# 4T_-.net
KiCad netlist of a schematic drawn in EasyEDA Pro
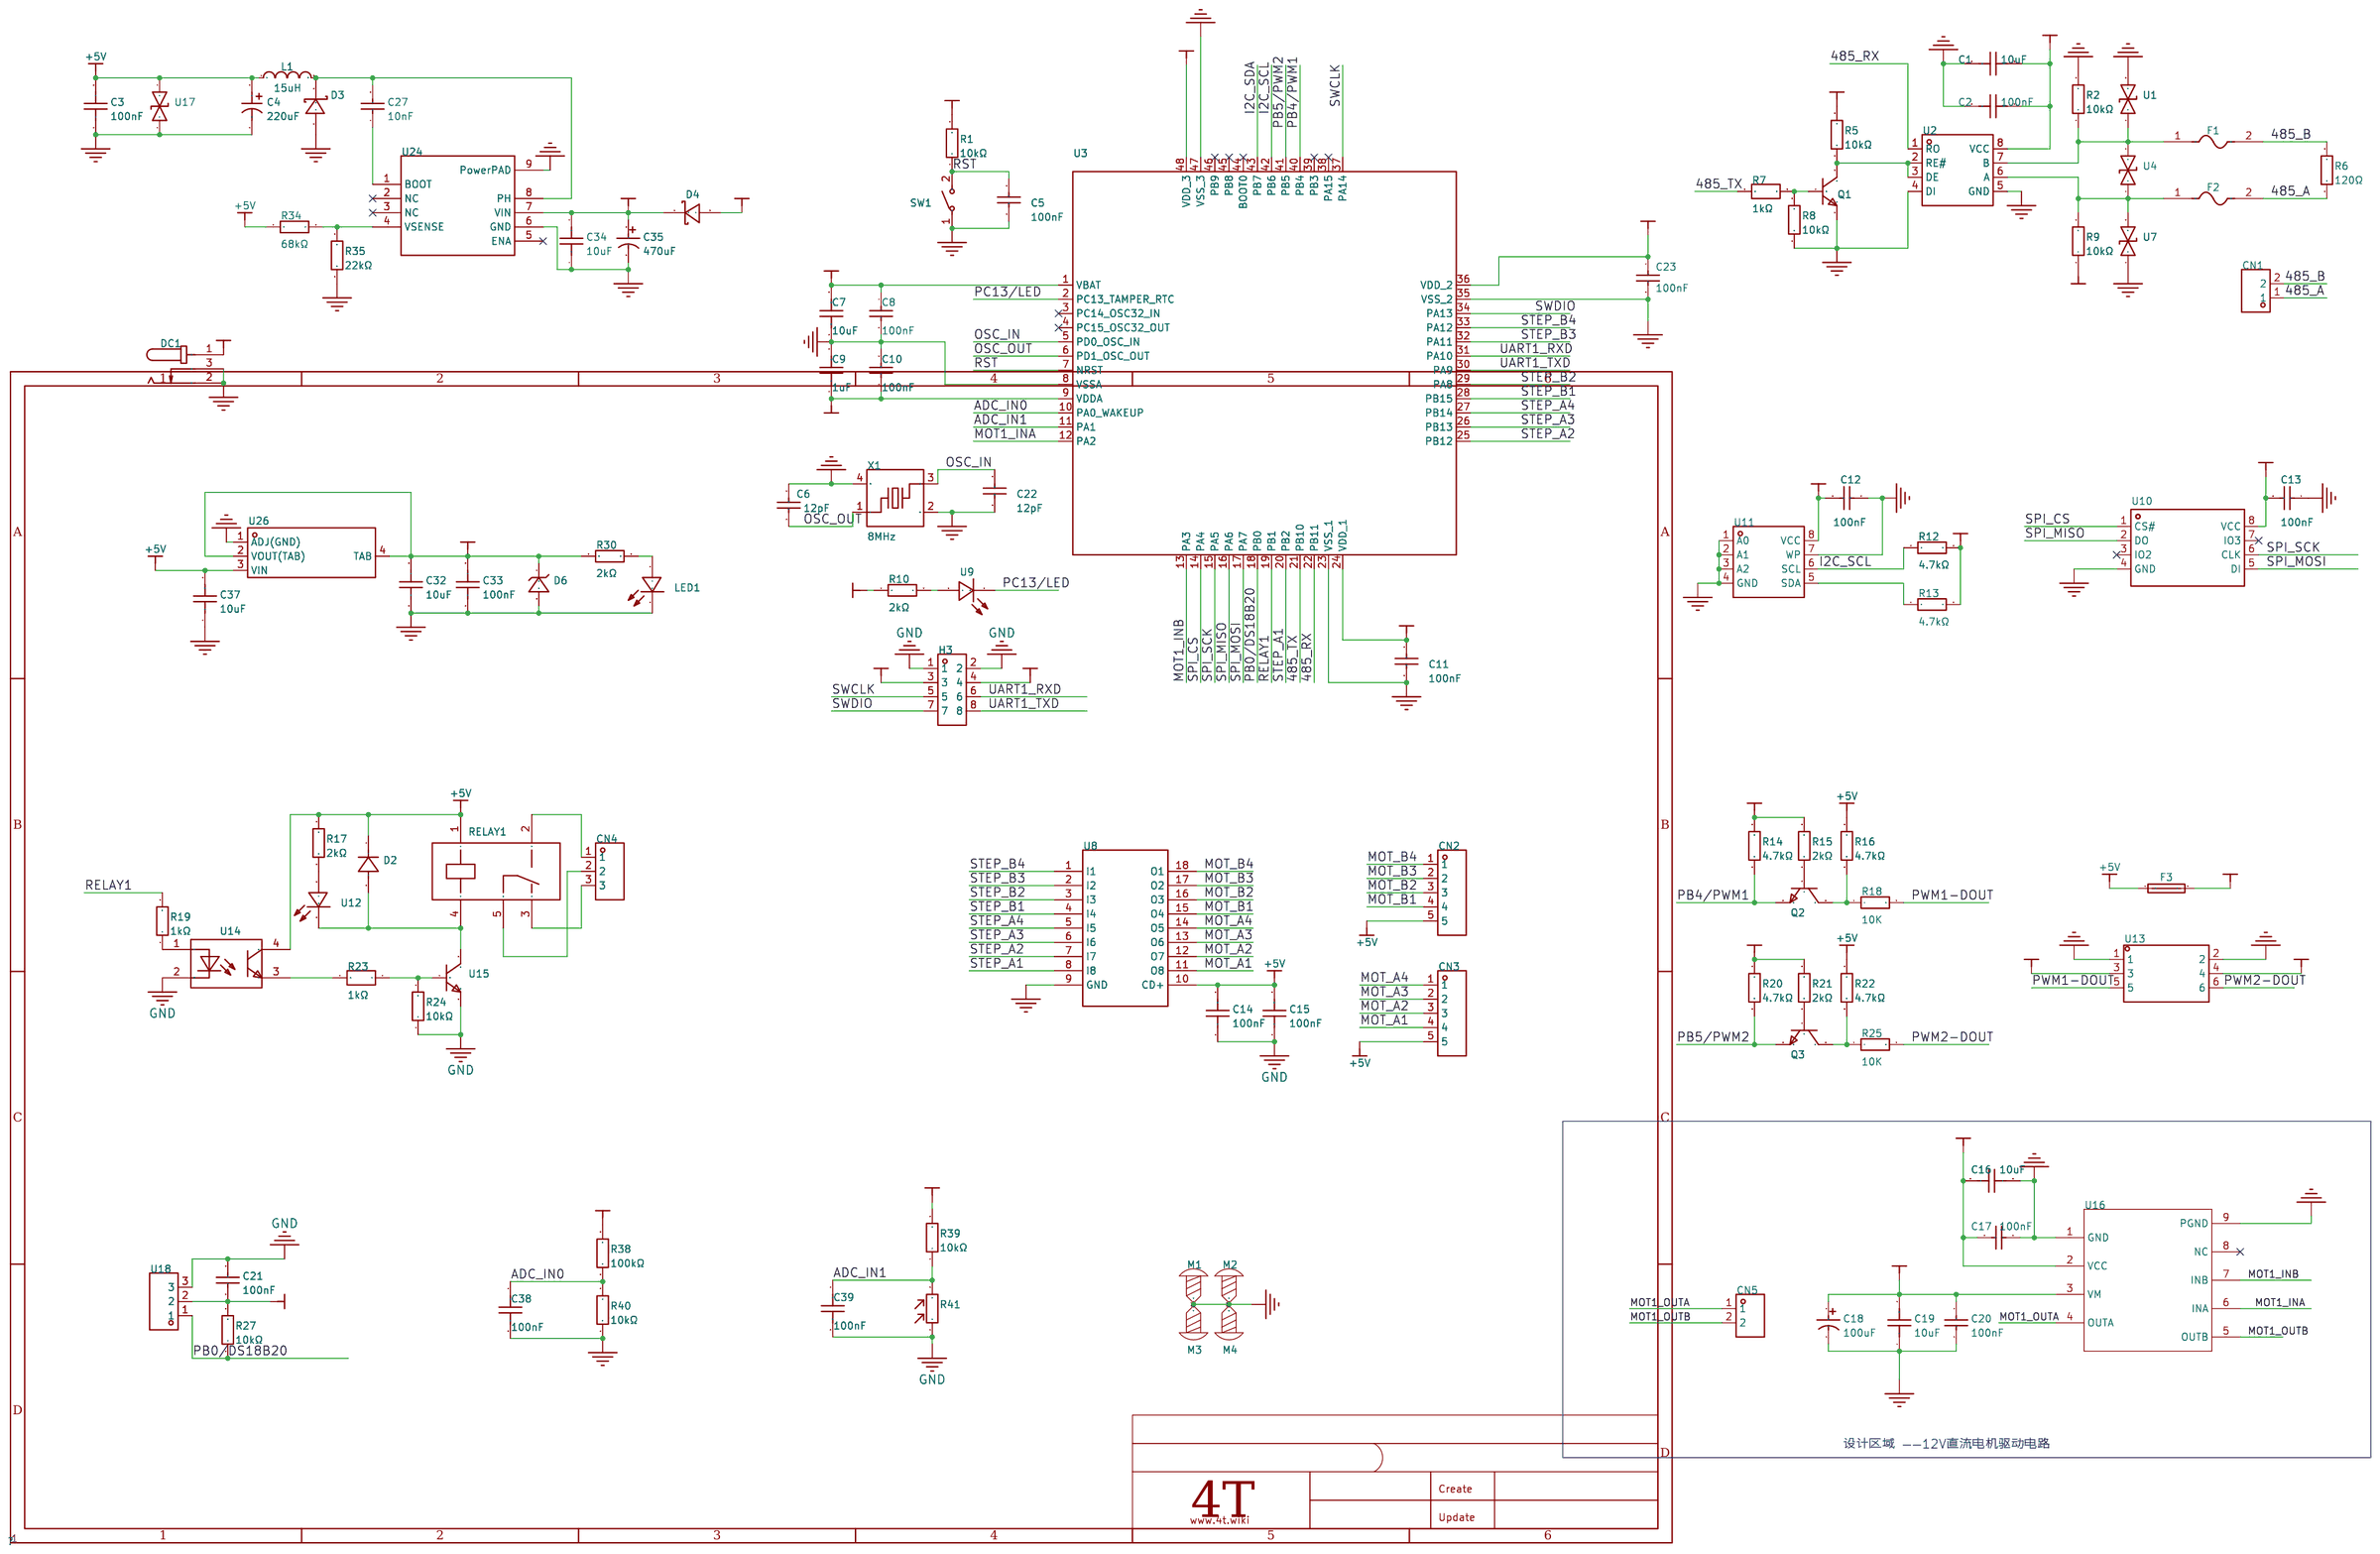
[diagram p0: schematic sheet]

(export (version "E")
  (design (tool "Eeschema 10.0.6"))
  (components
    (comp (ref "C1")
      (value "10uF")
      (footprint "easyedapro:C0603")
      (fields
        (field (name "Manufacturer Part") "CC0603KRX5R6BB106")
        (field (name "Manufacturer") "YAGEO(国巨)")
      )
      (libsource (lib "easyedapro") (part "CC0603KRX5R6BB106"))
    )
    (comp (ref "C2") (value "100nF") (libsource (lib "easyedapro") (part "CC0603KRX7R9BB104")))
    (comp (ref "C3")
      (value "100nF")
      (footprint "easyedapro:C0805")
      (fields
        (field (name "Manufacturer Part") "CC0805KRX7R9BB104")
        (field (name "Manufacturer") "YAGEO(国巨)")
      )
      (libsource (lib "easyedapro") (part "CC0805KRX7R9BB104"))
    )
    (comp (ref "C4")
      (value "220uF")
      (footprint "easyedapro:CAP-SMD_BD6.3-L6.6-W6.6-FD")
      (fields (field (name "Manufacturer Part") "189RV0019") (field (name "Manufacturer") "KNSCHA(科尼盛)"))
      (libsource (lib "easyedapro") (part "189RV0019"))
    )
    (comp (ref "C5") (value "100nF") (libsource (lib "easyedapro") (part "CC0603KRX7R8BB104")))
    (comp (ref "C6")
      (value "12pF")
      (footprint "easyedapro:C0603")
      (fields
        (field (name "Manufacturer Part") "CL10C120JB8NNNC")
        (field (name "Manufacturer") "SAMSUNG(三星)")
      )
      (libsource (lib "easyedapro") (part "CL10C120JB8NNNC"))
    )
    (comp (ref "C7")
      (value "10uF")
      (footprint "easyedapro:C0603")
      (fields
        (field (name "Manufacturer Part") "CL10A106KP8NNNC")
        (field (name "Manufacturer") "SAMSUNG(三星)")
      )
      (libsource (lib "easyedapro") (part "CL10A106KP8NNNC"))
    )
    (comp (ref "C8") (value "100nF") (libsource (lib "easyedapro") (part "CC0603KRX7R8BB104")))
    (comp (ref "C9")
      (value "1uF")
      (footprint "easyedapro:C0603")
      (fields
        (field (name "Manufacturer Part") "CC0603KRX7R9BB105")
        (field (name "Manufacturer") "YAGEO(国巨)")
      )
      (libsource (lib "easyedapro") (part "CC0603KRX7R9BB105"))
    )
    (comp (ref "C10") (value "100nF") (libsource (lib "easyedapro") (part "CC0603KRX7R8BB104")))
    (comp (ref "C11") (value "100nF") (libsource (lib "easyedapro") (part "CC0603KRX7R8BB104")))
    (comp (ref "C12") (value "100nF") (libsource (lib "easyedapro") (part "CC0603KRX7R8BB104")))
    (comp (ref "C13") (value "100nF") (libsource (lib "easyedapro") (part "CC0603KRX7R8BB104")))
    (comp (ref "C14")
      (value "100nF")
      (footprint "easyedapro:C0805")
      (fields
        (field (name "Manufacturer Part") "CL21A226MAQNNNE")
        (field (name "Manufacturer") "SAMSUNG(三星)")
      )
      (libsource (lib "easyedapro") (part "CL21A226MAQNNNE"))
    )
    (comp (ref "C15")
      (value "100nF")
      (footprint "easyedapro:C0805")
      (fields
        (field (name "Manufacturer Part") "CL21A226MAQNNNE")
        (field (name "Manufacturer") "SAMSUNG(三星)")
      )
      (libsource (lib "easyedapro") (part "CL21A226MAQNNNE"))
    )
    (comp (ref "C16")
      (value "10uF")
      (footprint "easyedapro:C0603")
      (fields
        (field (name "Manufacturer Part") "CL10A106MA8NRNC")
        (field (name "Manufacturer") "SAMSUNG(三星)")
      )
      (libsource (lib "easyedapro") (part "CL10A106MA8NRNC"))
    )
    (comp (ref "C17")
      (value "100nF")
      (footprint "easyedapro:C0603")
      (fields
        (field (name "Manufacturer Part") "CC0603KRX7R8BB104")
        (field (name "Manufacturer") "YAGEO(国巨)")
      )
      (libsource (lib "easyedapro") (part "CC0603KRX7R8BB104"))
    )
    (comp (ref "C18")
      (value "100uF")
      (footprint "easyedapro:CAP-SMD_BD6.3-L6.6-W6.6-LS7.2-R-RD")
      (fields (field (name "Manufacturer Part") "RVE1V101M0607") (field (name "Manufacturer") "ROQANG(容强)"))
      (libsource (lib "easyedapro") (part "RVE1V101M0607-C99837"))
    )
    (comp (ref "C19")
      (value "10uF")
      (footprint "easyedapro:C0603")
      (fields
        (field (name "Manufacturer Part") "CL10A106MA8NRNC")
        (field (name "Manufacturer") "SAMSUNG(三星)")
      )
      (libsource (lib "easyedapro") (part "CL10A106MA8NRNC"))
    )
    (comp (ref "C20")
      (value "100nF")
      (footprint "easyedapro:C0603")
      (fields
        (field (name "Manufacturer Part") "CC0603KRX7R8BB104")
        (field (name "Manufacturer") "YAGEO(国巨)")
      )
      (libsource (lib "easyedapro") (part "CC0603KRX7R8BB104"))
    )
    (comp (ref "C21") (value "100nF") (libsource (lib "easyedapro") (part "CC0603KRX7R8BB104")))
    (comp (ref "C22")
      (value "12pF")
      (footprint "easyedapro:C0603")
      (fields
        (field (name "Manufacturer Part") "CL10C120JB8NNNC")
        (field (name "Manufacturer") "SAMSUNG(三星)")
      )
      (libsource (lib "easyedapro") (part "CL10C120JB8NNNC"))
    )
    (comp (ref "C23") (value "100nF") (libsource (lib "easyedapro") (part "CC0603KRX7R8BB104")))
    (comp (ref "C27")
      (value "10nF")
      (footprint "easyedapro:C0603")
      (fields (field (name "Manufacturer Part") "0603B103K500NT") (field (name "Manufacturer") "FH(风华)"))
      (libsource (lib "easyedapro") (part "0603B103K500NT"))
    )
    (comp (ref "C32")
      (value "10uF")
      (footprint "easyedapro:C0603")
      (fields
        (field (name "Manufacturer Part") "CC0603MRX5R8BB106")
        (field (name "Manufacturer") "YAGEO(国巨)")
      )
      (libsource (lib "easyedapro") (part "CC0603MRX5R8BB106"))
    )
    (comp (ref "C33") (value "100nF") (libsource (lib "") (part "CC0603KRX7R9BB104_1")))
    (comp (ref "C34")
      (value "10uF")
      (footprint "easyedapro:C0805")
      (fields
        (field (name "Manufacturer Part") "GRM21BR61H106KE43L")
        (field (name "Manufacturer") "muRata(村田)")
      )
      (libsource (lib "easyedapro") (part "GRM21BR61H106KE43L"))
    )
    (comp (ref "C35")
      (value "470uF")
      (footprint "easyedapro:CAP-SMD_BD10.0-L10.3-W10.3-LS11.0-R-RD")
      (fields (field (name "Manufacturer Part") "RVT1V471M1010") (field (name "Manufacturer") "ROQANG(容强)"))
      (libsource (lib "easyedapro") (part "RVT1V471M1010-C72519"))
    )
    (comp (ref "C37")
      (value "10uF")
      (footprint "easyedapro:C0603")
      (fields
        (field (name "Manufacturer Part") "CC0603MRX5R8BB106")
        (field (name "Manufacturer") "YAGEO(国巨)")
      )
      (libsource (lib "easyedapro") (part "CC0603MRX5R8BB106"))
    )
    (comp (ref "C38")
      (value "100nF")
      (footprint "easyedapro:C0603")
      (fields
        (field (name "Manufacturer Part") "CC0603KRX7R9BB104")
        (field (name "Manufacturer") "YAGEO(国巨)")
      )
      (libsource (lib "easyedapro") (part "CC0603KRX7R9BB104"))
    )
    (comp (ref "C39")
      (value "100nF")
      (footprint "easyedapro:C0603")
      (fields
        (field (name "Manufacturer Part") "CC0603KRX7R9BB104")
        (field (name "Manufacturer") "YAGEO(国巨)")
      )
      (libsource (lib "easyedapro") (part "CC0603KRX7R9BB104"))
    )
    (comp (ref "CN1")
      (value "~")
      (footprint "easyedapro:CONN-TH_P5.00_KF2EDGR-5.0-2P")
      (fields (field (name "Manufacturer Part") "KF2EDGR-5.0-2P") (field (name "Manufacturer") "KEFA(科发)"))
      (libsource (lib "easyedapro") (part "KF2EDGR-5.0-2P"))
    )
    (comp (ref "CN2")
      (value "~")
      (footprint "easyedapro:CONN-TH_5P-P2.54_XH-5AW_C2908614")
      (fields (field (name "Manufacturer Part") "XH-5AW") (field (name "Manufacturer") "HCTL(华灿天禄)"))
      (libsource (lib "easyedapro") (part "XH-5AW_C2908614"))
    )
    (comp (ref "CN3")
      (value "~")
      (footprint "easyedapro:CONN-TH_5P-P2.54_XH-5AW_C2908614")
      (fields (field (name "Manufacturer Part") "XH-5AW") (field (name "Manufacturer") "HCTL(华灿天禄)"))
      (libsource (lib "easyedapro") (part "XH-5AW_C2908614"))
    )
    (comp (ref "CN4")
      (value "~")
      (footprint "easyedapro:CONN-TH_3P-P5.00_KF2EDGR-5.0-3P")
      (fields (field (name "Manufacturer Part") "KF2EDGR-5.0-3P") (field (name "Manufacturer") "KEFA(科发)"))
      (libsource (lib "easyedapro") (part "KF2EDGR-5.0-3P"))
    )
    (comp (ref "CN5")
      (value "~")
      (footprint "easyedapro:CONN-TH_2P-P2.50_ZX-XH2.54-2PWZ")
      (fields
        (field (name "Manufacturer Part") "ZX-XH2.54-2PWZ")
        (field (name "Manufacturer") "Megastar(兆星)")
      )
      (libsource (lib "easyedapro") (part "ZX-XH2.54-2PWZ"))
    )
    (comp (ref "D2") (value "1N4007") (libsource (lib "easyedapro") (part "1N4007_C727081")))
    (comp (ref "D3")
      (value "SS34")
      (footprint "easyedapro:SMA_L4.3-W2.6-LS5.2-RD")
      (fields (field (name "Manufacturer") "MDD(辰达半导体)"))
      (libsource (lib "easyedapro") (part "SS34_C8678"))
    )
    (comp (ref "D4")
      (value "SS34")
      (footprint "easyedapro:SMA_L4.3-W2.6-LS5.2-RD")
      (fields (field (name "Manufacturer") "MDD(辰达半导体)"))
      (libsource (lib "easyedapro") (part "SS34_C8678"))
    )
    (comp (ref "D6")
      (value "~")
      (footprint "easyedapro:SMB_L4.3-W3.6-LS5.3-RD")
      (fields (field (name "Manufacturer Part") "SMBJ3.3A") (field (name "Manufacturer") "RUILON(瑞隆源)"))
      (libsource (lib "easyedapro") (part "SMBJ3.3A_C2990571"))
    )
    (comp (ref "DC1")
      (value "~")
      (footprint "easyedapro:CONN-TH_DC-005-2.5A-2.0")
      (fields
        (field (name "Manufacturer Part") "DC-005-2.5A-2.0")
        (field (name "Manufacturer") "XKB Connectivity(中国星坤)")
      )
      (libsource (lib "easyedapro") (part "DC-005-2.5A-2.0"))
    )
    (comp (ref "F1")
      (value "~")
      (footprint "easyedapro:F0805")
      (fields (field (name "Manufacturer Part") "0805L100/12AR") (field (name "Manufacturer") "LUTE(陆特)"))
      (libsource (lib "easyedapro") (part "0805l100/12ar"))
    )
    (comp (ref "F2")
      (value "~")
      (footprint "easyedapro:F0805")
      (fields (field (name "Manufacturer Part") "0805L100/12AR") (field (name "Manufacturer") "LUTE(陆特)"))
      (libsource (lib "easyedapro") (part "0805l100/12ar"))
    )
    (comp (ref "F3")
      (value "~")
      (footprint "easyedapro:F0603")
      (fields (field (name "Manufacturer Part") "BSMD0603L-100") (field (name "Manufacturer") "BHFUSE(佰宏)"))
      (libsource (lib "easyedapro") (part "BSMD0603L-100"))
    )
    (comp (ref "H3")
      (value "~")
      (footprint "easyedapro:HDR-TH_8P-P2.54-V-M-R2-C4-S2.54")
      (fields (field (name "Manufacturer Part") "PZ254V-12-8P") (field (name "Manufacturer") "XFCN(兴飞)"))
      (libsource (lib "easyedapro") (part "PZ254V-12-8P"))
    )
    (comp (ref "L1")
      (value "15uH")
      (footprint "easyedapro:IND-SMD_L7.1-W6.6_SLO0618H")
      (fields
        (field (name "Manufacturer Part") "SLO0630H150MTT")
        (field (name "Manufacturer") "Sunltech(韩国顺磁)")
      )
      (libsource (lib "easyedapro") (part "SLO0630H150MTT"))
    )
    (comp (ref "LED1")
      (value "~")
      (footprint "easyedapro:LED0603-RD")
      (fields (field (name "Manufacturer Part") "KT-0603R") (field (name "Manufacturer") "KENTO"))
      (libsource (lib "easyedapro") (part "KT-0603R"))
    )
    (comp (ref "M1")
      (value "~")
      (footprint "easyedapro:LQ_M3螺丝")
      (description "Round,210")
      (libsource (lib "easyedapro") (part "M3螺丝孔"))
    )
    (comp (ref "M2")
      (value "~")
      (footprint "easyedapro:LQ_M3螺丝")
      (description "Round,210")
      (libsource (lib "easyedapro") (part "M3螺丝孔"))
    )
    (comp (ref "M3")
      (value "~")
      (footprint "easyedapro:LQ_M3螺丝")
      (description "Round,210")
      (libsource (lib "easyedapro") (part "M3螺丝孔"))
    )
    (comp (ref "M4")
      (value "~")
      (footprint "easyedapro:LQ_M3螺丝")
      (description "Round,210")
      (libsource (lib "easyedapro") (part "M3螺丝孔"))
    )
    (comp (ref "Q1")
      (value "~")
      (footprint "easyedapro:SOT-23-3_L2.9-W1.3-P1.90-LS2.4-BR")
      (fields (field (name "Manufacturer Part") "MMBT3904") (field (name "Manufacturer") "宏迦橙"))
      (libsource (lib "easyedapro") (part "MMBT3904_C7420353"))
    )
    (comp (ref "Q2")
      (value "S8050-J3Y")
      (footprint "easyedapro:SOT-23-3_L2.9-W1.6-P1.90-LS2.8-BR")
      (fields (field (name "Manufacturer Part") "S8050") (field (name "Manufacturer") "CJ(江苏长电/长晶)"))
      (libsource (lib "easyedapro") (part "S8050_C105433"))
    )
    (comp (ref "Q3")
      (value "S8050-J3Y")
      (footprint "easyedapro:SOT-23-3_L2.9-W1.6-P1.90-LS2.8-BR")
      (fields (field (name "Manufacturer Part") "S8050") (field (name "Manufacturer") "CJ(江苏长电/长晶)"))
      (libsource (lib "easyedapro") (part "S8050_C105433"))
    )
    (comp (ref "R1")
      (value "10kΩ")
      (footprint "easyedapro:R0603")
      (fields
        (field (name "Manufacturer Part") "0603WAF1002T5E")
        (field (name "Manufacturer") "UNI-ROYAL(厚声)")
      )
      (libsource (lib "easyedapro") (part "0603WAF1002T5E"))
    )
    (comp (ref "R2") (value "10kΩ") (libsource (lib "easyedapro") (part "RC0603JR-0710KL")))
    (comp (ref "R5")
      (value "10kΩ")
      (footprint "easyedapro:R0603")
      (fields (field (name "Manufacturer Part") "RC0603JR-0710KL") (field (name "Manufacturer") "YAGEO(国巨)"))
      (libsource (lib "easyedapro") (part "RC0603JR-0710KL"))
    )
    (comp (ref "R6")
      (value "120Ω")
      (footprint "easyedapro:R0805")
      (fields
        (field (name "Manufacturer Part") "0805W8F1200T5E")
        (field (name "Manufacturer") "UNI-ROYAL(厚声)")
      )
      (libsource (lib "easyedapro") (part "0805W8F1200T5E"))
    )
    (comp (ref "R7")
      (value "1kΩ")
      (footprint "easyedapro:R0603")
      (fields (field (name "Manufacturer Part") "RT0603BRE071KL") (field (name "Manufacturer") "YAGEO(国巨)"))
      (libsource (lib "easyedapro") (part "RT0603BRE071KL"))
    )
    (comp (ref "R8")
      (value "10kΩ")
      (footprint "easyedapro:R0603")
      (fields (field (name "Manufacturer Part") "RC0603JR-0710KL") (field (name "Manufacturer") "YAGEO(国巨)"))
      (libsource (lib "easyedapro") (part "RC0603JR-0710KL"))
    )
    (comp (ref "R9") (value "10kΩ") (libsource (lib "easyedapro") (part "RC0603JR-0710KL")))
    (comp (ref "R10")
      (value "2kΩ")
      (footprint "easyedapro:R0603")
      (fields
        (field (name "Manufacturer Part") "0603WAF2001T5E")
        (field (name "Manufacturer") "UNI-ROYAL(厚声)")
      )
      (libsource (lib "easyedapro") (part "0603WAF2001T5E"))
    )
    (comp (ref "R12")
      (value "4.7kΩ")
      (footprint "easyedapro:R0603")
      (fields (field (name "Manufacturer Part") "RC0603FR-074K7L") (field (name "Manufacturer") "YAGEO(国巨)"))
      (libsource (lib "easyedapro") (part "RC0603FR-074K7L"))
    )
    (comp (ref "R13")
      (value "4.7kΩ")
      (footprint "easyedapro:R0603")
      (fields (field (name "Manufacturer Part") "RC0603FR-074K7L") (field (name "Manufacturer") "YAGEO(国巨)"))
      (libsource (lib "easyedapro") (part "RC0603FR-074K7L"))
    )
    (comp (ref "R14")
      (value "4.7kΩ")
      (footprint "easyedapro:R0603")
      (fields (field (name "Manufacturer Part") "RC0603FR-074K7L") (field (name "Manufacturer") "YAGEO(国巨)"))
      (libsource (lib "easyedapro") (part "RC0603FR-074K7L"))
    )
    (comp (ref "R15")
      (value "2kΩ")
      (footprint "easyedapro:R0603")
      (fields (field (name "Manufacturer Part") "RC0603FR-072KL") (field (name "Manufacturer") "YAGEO(国巨)"))
      (libsource (lib "easyedapro") (part "RC0603FR-072KL"))
    )
    (comp (ref "R16")
      (value "4.7kΩ")
      (footprint "easyedapro:R0603")
      (fields (field (name "Manufacturer Part") "RC0603FR-074K7L") (field (name "Manufacturer") "YAGEO(国巨)"))
      (libsource (lib "easyedapro") (part "RC0603FR-074K7L"))
    )
    (comp (ref "R17")
      (value "2kΩ")
      (footprint "easyedapro:R0603")
      (fields
        (field (name "Manufacturer Part") "0603WAF2001T5E")
        (field (name "Manufacturer") "UNI-ROYAL(厚声)")
      )
      (libsource (lib "easyedapro") (part "0603WAF2001T5E"))
    )
    (comp (ref "R18")
      (value "10K")
      (footprint "easyedapro:R0603")
      (fields (field (name "Manufacturer Part") "RC0603FR-071KL") (field (name "Manufacturer") "YAGEO(国巨)"))
      (libsource (lib "easyedapro") (part "RC0603FR-071KL"))
    )
    (comp (ref "R19") (value "1kΩ") (libsource (lib "easyedapro") (part "RC0603FR-071KL")))
    (comp (ref "R20")
      (value "4.7kΩ")
      (footprint "easyedapro:R0603")
      (fields (field (name "Manufacturer Part") "RC0603FR-074K7L") (field (name "Manufacturer") "YAGEO(国巨)"))
      (libsource (lib "easyedapro") (part "RC0603FR-074K7L"))
    )
    (comp (ref "R21")
      (value "2kΩ")
      (footprint "easyedapro:R0603")
      (fields (field (name "Manufacturer Part") "RC0603FR-072KL") (field (name "Manufacturer") "YAGEO(国巨)"))
      (libsource (lib "easyedapro") (part "RC0603FR-072KL"))
    )
    (comp (ref "R22")
      (value "4.7kΩ")
      (footprint "easyedapro:R0603")
      (fields (field (name "Manufacturer Part") "RC0603FR-074K7L") (field (name "Manufacturer") "YAGEO(国巨)"))
      (libsource (lib "easyedapro") (part "RC0603FR-074K7L"))
    )
    (comp (ref "R23")
      (value "1kΩ")
      (footprint "easyedapro:R0603")
      (fields (field (name "Manufacturer Part") "RT0603BRE071KL") (field (name "Manufacturer") "YAGEO(国巨)"))
      (libsource (lib "easyedapro") (part "RT0603BRE071KL"))
    )
    (comp (ref "R24")
      (value "10kΩ")
      (footprint "easyedapro:R0603")
      (fields
        (field (name "Manufacturer Part") "0603WAF1002T5E")
        (field (name "Manufacturer") "UNI-ROYAL(厚声)")
      )
      (libsource (lib "easyedapro") (part "0603WAF1002T5E"))
    )
    (comp (ref "R25")
      (value "10K")
      (footprint "easyedapro:R0603")
      (fields (field (name "Manufacturer Part") "RC0603FR-071KL") (field (name "Manufacturer") "YAGEO(国巨)"))
      (libsource (lib "easyedapro") (part "RC0603FR-071KL"))
    )
    (comp (ref "R27")
      (value "10kΩ")
      (footprint "easyedapro:R0603")
      (fields
        (field (name "Manufacturer Part") "0603WAF1002T5E")
        (field (name "Manufacturer") "UNI-ROYAL(厚声)")
      )
      (libsource (lib "easyedapro") (part "0603WAF1002T5E"))
    )
    (comp (ref "R30") (value "2kΩ") (libsource (lib "easyedapro") (part "0603WAF2001T5E")))
    (comp (ref "R34")
      (value "68kΩ")
      (footprint "easyedapro:R0603")
      (fields
        (field (name "Manufacturer Part") "0603WAF6802T5E")
        (field (name "Manufacturer") "UNI-ROYAL(厚声)")
      )
      (libsource (lib "easyedapro") (part "0603WAF6802T5E"))
    )
    (comp (ref "R35")
      (value "22kΩ")
      (footprint "easyedapro:R0603")
      (fields (field (name "Manufacturer Part") "RC0603FR-0722KL") (field (name "Manufacturer") "YAGEO(国巨)"))
      (libsource (lib "easyedapro") (part "RC0603FR-0722KL"))
    )
    (comp (ref "R38")
      (value "100kΩ")
      (footprint "easyedapro:R0603")
      (fields (field (name "Manufacturer Part") "RC0603FR-07100KL") (field (name "Manufacturer") "YAGEO(国巨)"))
      (libsource (lib "easyedapro") (part "RC0603FR-07100KL"))
    )
    (comp (ref "R39")
      (value "10kΩ")
      (footprint "easyedapro:R0603")
      (fields
        (field (name "Manufacturer Part") "0603WAF1002T5E")
        (field (name "Manufacturer") "UNI-ROYAL(厚声)")
      )
      (libsource (lib "easyedapro") (part "0603WAF1002T5E"))
    )
    (comp (ref "R40")
      (value "10kΩ")
      (footprint "easyedapro:R0603")
      (fields
        (field (name "Manufacturer Part") "0603WAF1002T5E")
        (field (name "Manufacturer") "UNI-ROYAL(厚声)")
      )
      (libsource (lib "easyedapro") (part "0603WAF1002T5E"))
    )
    (comp (ref "R41") (value "~") (libsource (lib "easyedapro") (part "GL5516")))
    (comp (ref "RELAY1")
      (value "~")
      (footprint "easyedapro:RELAY-TH_SRD-XXVDC-XL-C")
      (fields (field (name "Manufacturer Part") "SRD-12VDC-SL-C") (field (name "Manufacturer") "松乐"))
      (libsource (lib "easyedapro") (part "SRD-12VDC-SL-C"))
    )
    (comp (ref "SW1")
      (value "~")
      (footprint "easyedapro:SW-SMD_L6.0-W3.5-LS8.0")
      (fields
        (field (name "Manufacturer Part") "GT-TC060B-H025-L1")
        (field (name "Manufacturer") "G-Switch(品赞)")
      )
      (libsource (lib "easyedapro") (part "GT-TC060B-H025-L1"))
    )
    (comp (ref "U1")
      (value "~")
      (footprint "easyedapro:SOD-123FL_L2.8-W1.8-LS3.7-BI")
      (fields (field (name "Manufacturer Part") "SMF6.0CA") (field (name "Manufacturer") "Liown(里阳半导体)"))
      (libsource (lib "easyedapro") (part "SMF6.0CA_C2990473"))
    )
    (comp (ref "U2")
      (value "~")
      (footprint "easyedapro:SOP-8_L4.9-W3.9-P1.27-LS6.0-BL")
      (fields (field (name "Manufacturer Part") "SP3485EN-MS") (field (name "Manufacturer") "MSKSEMI(美森科)"))
      (libsource (lib "easyedapro") (part "SP3485EN-MS"))
    )
    (comp (ref "U3")
      (value "~")
      (footprint "easyedapro:TQFP-48_L7.0-W7.0-P0.50-LS9.0-BL")
      (fields
        (field (name "Manufacturer Part") "GD32F103C8T6")
        (field (name "Manufacturer") "GigaDevice(兆易创新)")
      )
      (libsource (lib "easyedapro") (part "GD32F103C8T6"))
    )
    (comp (ref "U4")
      (value "~")
      (footprint "easyedapro:SOD-123FL_L2.8-W1.8-LS3.7-BI")
      (fields (field (name "Manufacturer Part") "SMF6.0CA") (field (name "Manufacturer") "Liown(里阳半导体)"))
      (libsource (lib "easyedapro") (part "SMF6.0CA_C2990473"))
    )
    (comp (ref "U7")
      (value "~")
      (footprint "easyedapro:SOD-123FL_L2.8-W1.8-LS3.7-BI")
      (fields (field (name "Manufacturer Part") "SMF6.0CA") (field (name "Manufacturer") "Liown(里阳半导体)"))
      (libsource (lib "easyedapro") (part "SMF6.0CA_C2990473"))
    )
    (comp (ref "U8")
      (value "~")
      (footprint "easyedapro:DIP-18_L23.0-W6.5-P2.54-LS7.6-BL")
      (fields (field (name "Manufacturer Part") "ULN2803G-D18-T") (field (name "Manufacturer") "UTC(友顺)"))
      (libsource (lib "easyedapro") (part "ULN2803G-D18-T"))
    )
    (comp (ref "U9")
      (value "~")
      (footprint "easyedapro:LED-TH_BD3.9-P2.54-RD_GREEN")
      (fields (field (name "Manufacturer Part") "L-3N4GD") (field (name "Manufacturer") "PARALIGHT(光鼎)"))
      (libsource (lib "easyedapro") (part "L-3N4GD"))
    )
    (comp (ref "U10")
      (value "~")
      (footprint "easyedapro:SOIC-8_L5.3-W5.3-P1.27-LS8.0-BL")
      (fields (field (name "Manufacturer Part") "W25Q128JVSIQ") (field (name "Manufacturer") "WINBOND(华邦)"))
      (libsource (lib "easyedapro") (part "W25Q128JVSIQTR"))
    )
    (comp (ref "U11")
      (value "AT24C02")
      (footprint "easyedapro:SOP-8_L5.0-W4.0-P1.27-LS6.0-BL")
      (fields (field (name "Manufacturer") "IDCHIP(英锐芯)"))
      (libsource (lib "easyedapro") (part "AT24C02"))
    )
    (comp (ref "U12")
      (value "~")
      (footprint "easyedapro:LED-TH_BD3.9-P2.54-RD_GREEN")
      (fields (field (name "Manufacturer Part") "L-3N4GD") (field (name "Manufacturer") "PARALIGHT(光鼎)"))
      (libsource (lib "easyedapro") (part "L-3N4GD"))
    )
    (comp (ref "U13")
      (value "~")
      (footprint "easyedapro:HDR-TH_6P-P2.54-H-R2-C3-S2.54-W10.0_MTP125-203R1")
      (fields (field (name "Manufacturer Part") "MTP125-1203R1") (field (name "Manufacturer") "MINTRON(明硕)"))
      (libsource (lib "easyedapro") (part "MTP125-203R1"))
    )
    (comp (ref "U14")
      (value "GX817C-S")
      (footprint "easyedapro:SOP-4_L6.5-W4.6-P2.54-LS10.2-TR")
      (fields (field (name "Manufacturer") "国芯佳品"))
      (libsource (lib "easyedapro") (part "GX817C-S"))
    )
    (comp (ref "U15")
      (value "~")
      (footprint "easyedapro:SOT-23-3_L2.9-W1.3-P1.90-LS2.4-BR")
      (fields (field (name "Manufacturer Part") "SS8050") (field (name "Manufacturer") "宏迦橙"))
      (libsource (lib "easyedapro") (part "SS8050_C7420370"))
    )
    (comp (ref "U16") (value "~") (libsource (lib "easyedapro") (part "BDR")))
    (comp (ref "U17")
      (value "~")
      (footprint "easyedapro:SOD-123FL_L2.8-W1.8-LS3.7-BI")
      (fields (field (name "Manufacturer Part") "SMF6.0CA") (field (name "Manufacturer") "Liown(里阳半导体)"))
      (libsource (lib "easyedapro") (part "SMF6.0CA_C2990473"))
    )
    (comp (ref "U18")
      (value "~")
      (footprint "easyedapro:CONN-TH_3P-P2.50_BX-XH2.54-3PWZ")
      (fields (field (name "Manufacturer Part") "BX-XH2.54-3PWZ") (field (name "Manufacturer") "Bossie(博锡)"))
      (libsource (lib "easyedapro") (part "BX-XH2.54-3P WZ"))
    )
    (comp (ref "U24")
      (value "~")
      (footprint "easyedapro:ESOP-8_L4.9-W3.9-P1.27-LS6.0-TL-EP")
      (fields (field (name "Manufacturer Part") "TPS5430DDAR") (field (name "Manufacturer") "TI(德州仪器)"))
      (libsource (lib "easyedapro") (part "TPS5430DDAR"))
    )
    (comp (ref "U26")
      (value "~")
      (footprint "easyedapro:SOT-223-4_L6.5-W3.5-P2.30-LS7.0-BR")
      (fields (field (name "Manufacturer Part") "AMS1117-3.3") (field (name "Manufacturer") "UMW(友台半导体)"))
      (libsource (lib "easyedapro") (part "AMS1117-3.3_C347222"))
    )
    (comp (ref "X1")
      (value "8MHz")
      (footprint "easyedapro:CRYSTAL-SMD_4P-L3.2-W2.5-BL")
      (fields (field (name "Manufacturer Part") "X32258MOB4SI") (field (name "Manufacturer") "YXC(扬兴晶振)"))
      (libsource (lib "easyedapro") (part "X32258MOB4SI"))
    )
  )
  (nets
    (net (code "1") (name "+5V") (class "Default")
      (node (ref "C14") (pin "2") (pinfunction "2_2") (pintype "unspecified"))
      (node (ref "C15") (pin "2") (pinfunction "2_2") (pintype "unspecified"))
      (node (ref "C3") (pin "2") (pinfunction "2_2") (pintype "unspecified"))
      (node (ref "C37") (pin "2") (pinfunction "2_2") (pintype "input"))
      (node (ref "C4") (pin "1") (pinfunction "1_1") (pintype "input"))
      (node (ref "CN2") (pin "5") (pinfunction "5_5") (pintype "unspecified"))
      (node (ref "CN3") (pin "5") (pinfunction "5_5") (pintype "unspecified"))
      (node (ref "D2") (pin "1") (pinfunction "K_1") (pintype "unspecified"))
      (node (ref "F3") (pin "1") (pinfunction "1_1") (pintype "unspecified"))
      (node (ref "L1") (pin "1") (pinfunction "1_1") (pintype "unspecified"))
      (node (ref "R16") (pin "1") (pinfunction "1_1") (pintype "input"))
      (node (ref "R17") (pin "1") (pinfunction "1_1") (pintype "input"))
      (node (ref "R22") (pin "1") (pinfunction "1_1") (pintype "input"))
      (node (ref "R34") (pin "1") (pinfunction "1_1") (pintype "input"))
      (node (ref "RELAY1") (pin "1") (pinfunction "1_1") (pintype "input"))
      (node (ref "U14") (pin "4") (pinfunction "C_4") (pintype "unspecified"))
      (node (ref "U17") (pin "1") (pinfunction "1_1") (pintype "unspecified"))
      (node (ref "U26") (pin "3") (pinfunction "VIN_3") (pintype "unspecified"))
      (node (ref "U8") (pin "10") (pinfunction "CD+_10") (pintype "unspecified"))
    )
    (net (code "2") (name "+5V-OUT") (class "Default")
      (node (ref "F3") (pin "2") (pinfunction "2_2") (pintype "unspecified"))
      (node (ref "U13") (pin "3") (pinfunction "3_3") (pintype "input"))
      (node (ref "U13") (pin "4") (pinfunction "4_4") (pintype "input"))
    )
    (net (code "3") (name "+12V") (class "Default")
      (node (ref "C18") (pin "1") (pinfunction "1_1") (pintype "input"))
      (node (ref "C19") (pin "2") (pinfunction "2_2") (pintype "unspecified"))
      (node (ref "C20") (pin "1") (pinfunction "1_1") (pintype "input"))
      (node (ref "C34") (pin "2") (pinfunction "2_2") (pintype "unspecified"))
      (node (ref "C35") (pin "1") (pinfunction "1_1") (pintype "input"))
      (node (ref "D4") (pin "1") (pinfunction "K_1") (pintype "unspecified"))
      (node (ref "U16") (pin "3") (pinfunction "VM_3") (pintype "input"))
      (node (ref "U24") (pin "7") (pinfunction "VIN_7") (pintype "unspecified"))
    )
    (net (code "4") (name "/485_A") (class "Default")
      (node (ref "CN1") (pin "1") (pinfunction "1_1") (pintype "unspecified"))
      (node (ref "F2") (pin "2") (pinfunction "2_2") (pintype "unspecified"))
      (node (ref "R6") (pin "1") (pinfunction "1_1") (pintype "input"))
    )
    (net (code "5") (name "/485_B") (class "Default")
      (node (ref "CN1") (pin "2") (pinfunction "2_2") (pintype "unspecified"))
      (node (ref "F1") (pin "2") (pinfunction "2_2") (pintype "unspecified"))
      (node (ref "R6") (pin "2") (pinfunction "2_2") (pintype "input"))
    )
    (net (code "6") (name "/485_RX") (class "Default")
      (node (ref "U2") (pin "1") (pinfunction "RO_1") (pintype "unspecified"))
      (node (ref "U3") (pin "22") (pinfunction "PB11_22") (pintype "unspecified"))
    )
    (net (code "7") (name "/485_TX") (class "Default")
      (node (ref "R7") (pin "1") (pinfunction "1_1") (pintype "unspecified"))
      (node (ref "U3") (pin "21") (pinfunction "PB10_21") (pintype "unspecified"))
    )
    (net (code "8") (name "/ADC_IN0") (class "Default")
      (node (ref "C38") (pin "1") (pinfunction "1_1") (pintype "unspecified"))
      (node (ref "R38") (pin "1") (pinfunction "1_1") (pintype "unspecified"))
      (node (ref "R40") (pin "2") (pinfunction "2_2") (pintype "input"))
      (node (ref "U3") (pin "10") (pinfunction "PA0_WAKEUP_10") (pintype "unspecified"))
    )
    (net (code "9") (name "/ADC_IN1") (class "Default")
      (node (ref "C39") (pin "1") (pinfunction "1_1") (pintype "unspecified"))
      (node (ref "R39") (pin "1") (pinfunction "1_1") (pintype "input"))
      (node (ref "R41") (pin "2") (pinfunction "2_2") (pintype "input"))
      (node (ref "U3") (pin "11") (pinfunction "PA1_11") (pintype "unspecified"))
    )
    (net (code "10") (name "/I2C_SCL") (class "Default")
      (node (ref "R12") (pin "1") (pinfunction "1_1") (pintype "input"))
      (node (ref "U11") (pin "6") (pinfunction "SCL_6") (pintype "unspecified"))
      (node (ref "U3") (pin "42") (pinfunction "PB6_42") (pintype "unspecified"))
    )
    (net (code "11") (name "/I2C_SDA") (class "Default")
      (node (ref "U3") (pin "43") (pinfunction "PB7_43") (pintype "unspecified"))
    )
    (net (code "12") (name "/MOT1_INA") (class "Default")
      (node (ref "U16") (pin "6") (pinfunction "INA_6") (pintype "input"))
      (node (ref "U3") (pin "12") (pinfunction "PA2_12") (pintype "unspecified"))
    )
    (net (code "13") (name "/MOT1_INB") (class "Default")
      (node (ref "U16") (pin "7") (pinfunction "INB_7") (pintype "input"))
      (node (ref "U3") (pin "13") (pinfunction "PA3_13") (pintype "unspecified"))
    )
    (net (code "14") (name "/MOT1_OUTA") (class "Default")
      (node (ref "CN5") (pin "1") (pinfunction "1_1") (pintype "unspecified"))
      (node (ref "U16") (pin "4") (pinfunction "OUTA_4") (pintype "input"))
    )
    (net (code "15") (name "/MOT1_OUTB") (class "Default")
      (node (ref "CN5") (pin "2") (pinfunction "2_2") (pintype "unspecified"))
      (node (ref "U16") (pin "5") (pinfunction "OUTB_5") (pintype "input"))
    )
    (net (code "16") (name "/MOT_A1") (class "Default")
      (node (ref "CN3") (pin "4") (pinfunction "4_4") (pintype "unspecified"))
      (node (ref "U8") (pin "11") (pinfunction "O8_11") (pintype "unspecified"))
    )
    (net (code "17") (name "/MOT_A2") (class "Default")
      (node (ref "CN3") (pin "3") (pinfunction "3_3") (pintype "unspecified"))
      (node (ref "U8") (pin "12") (pinfunction "O7_12") (pintype "unspecified"))
    )
    (net (code "18") (name "/MOT_A3") (class "Default")
      (node (ref "CN3") (pin "2") (pinfunction "2_2") (pintype "unspecified"))
      (node (ref "U8") (pin "13") (pinfunction "O6_13") (pintype "unspecified"))
    )
    (net (code "19") (name "/MOT_A4") (class "Default")
      (node (ref "CN3") (pin "1") (pinfunction "1_1") (pintype "unspecified"))
      (node (ref "U8") (pin "14") (pinfunction "O5_14") (pintype "unspecified"))
    )
    (net (code "20") (name "/MOT_B1") (class "Default")
      (node (ref "CN2") (pin "4") (pinfunction "4_4") (pintype "unspecified"))
      (node (ref "U8") (pin "15") (pinfunction "O4_15") (pintype "unspecified"))
    )
    (net (code "21") (name "/MOT_B2") (class "Default")
      (node (ref "CN2") (pin "3") (pinfunction "3_3") (pintype "unspecified"))
      (node (ref "U8") (pin "16") (pinfunction "O3_16") (pintype "unspecified"))
    )
    (net (code "22") (name "/MOT_B3") (class "Default")
      (node (ref "CN2") (pin "2") (pinfunction "2_2") (pintype "unspecified"))
      (node (ref "U8") (pin "17") (pinfunction "O2_17") (pintype "unspecified"))
    )
    (net (code "23") (name "/MOT_B4") (class "Default")
      (node (ref "CN2") (pin "1") (pinfunction "1_1") (pintype "unspecified"))
      (node (ref "U8") (pin "18") (pinfunction "O1_18") (pintype "unspecified"))
    )
    (net (code "24") (name "/OSC_IN") (class "Default")
      (node (ref "C22") (pin "2") (pinfunction "2_2") (pintype "input"))
      (node (ref "U3") (pin "5") (pinfunction "PD0_OSC_IN_5") (pintype "unspecified"))
      (node (ref "X1") (pin "3") (pinfunction "3_3") (pintype "input"))
    )
    (net (code "25") (name "/OSC_OUT") (class "Default")
      (node (ref "C6") (pin "1") (pinfunction "1_1") (pintype "input"))
      (node (ref "U3") (pin "6") (pinfunction "PD1_OSC_OUT_6") (pintype "unspecified"))
      (node (ref "X1") (pin "1") (pinfunction "1_1") (pintype "input"))
    )
    (net (code "26") (name "/PB0{slash}DS18B20") (class "Default")
      (node (ref "R27") (pin "1") (pinfunction "1_1") (pintype "input"))
      (node (ref "U18") (pin "1") (pinfunction "1_1") (pintype "unspecified"))
      (node (ref "U3") (pin "18") (pinfunction "PB0_18") (pintype "unspecified"))
    )
    (net (code "27") (name "/PB4{slash}PWM1") (class "Default")
      (node (ref "Q2") (pin "2") (pinfunction "2_2") (pintype "input"))
      (node (ref "R14") (pin "2") (pinfunction "2_2") (pintype "input"))
      (node (ref "U3") (pin "40") (pinfunction "PB4_40") (pintype "unspecified"))
    )
    (net (code "28") (name "/PB5{slash}PWM2") (class "Default")
      (node (ref "Q3") (pin "2") (pinfunction "2_2") (pintype "input"))
      (node (ref "R20") (pin "2") (pinfunction "2_2") (pintype "input"))
      (node (ref "U3") (pin "41") (pinfunction "PB5_41") (pintype "unspecified"))
    )
    (net (code "29") (name "/PC13{slash}LED") (class "Default")
      (node (ref "U3") (pin "2") (pinfunction "PC13_TAMPER_RTC_2") (pintype "unspecified"))
      (node (ref "U9") (pin "1") (pinfunction "C_1") (pintype "unspecified"))
    )
    (net (code "30") (name "/PWM1-DOUT") (class "Default")
      (node (ref "R18") (pin "2") (pinfunction "2_2") (pintype "input"))
      (node (ref "U13") (pin "5") (pinfunction "5_5") (pintype "input"))
    )
    (net (code "31") (name "/PWM2-DOUT") (class "Default")
      (node (ref "R25") (pin "2") (pinfunction "2_2") (pintype "input"))
      (node (ref "U13") (pin "6") (pinfunction "6_6") (pintype "input"))
    )
    (net (code "32") (name "/RELAY1") (class "Default")
      (node (ref "R19") (pin "2") (pinfunction "2_2") (pintype "input"))
      (node (ref "U3") (pin "19") (pinfunction "PB1_19") (pintype "unspecified"))
    )
    (net (code "33") (name "/RST") (class "Default")
      (node (ref "C5") (pin "1") (pinfunction "1_1") (pintype "input"))
      (node (ref "R1") (pin "1") (pinfunction "1_1") (pintype "input"))
      (node (ref "SW1") (pin "2") (pinfunction "2_2") (pintype "unspecified"))
      (node (ref "U3") (pin "7") (pinfunction "NRST_7") (pintype "unspecified"))
    )
    (net (code "34") (name "/SPI_CS") (class "Default")
      (node (ref "U10") (pin "1") (pinfunction "CS#_1") (pintype "unspecified"))
      (node (ref "U3") (pin "14") (pinfunction "PA4_14") (pintype "unspecified"))
    )
    (net (code "35") (name "/SPI_MISO") (class "Default")
      (node (ref "U10") (pin "2") (pinfunction "DO_2") (pintype "unspecified"))
      (node (ref "U3") (pin "16") (pinfunction "PA6_16") (pintype "unspecified"))
    )
    (net (code "36") (name "/SPI_MOSI") (class "Default")
      (node (ref "U10") (pin "5") (pinfunction "DI_5") (pintype "unspecified"))
      (node (ref "U3") (pin "17") (pinfunction "PA7_17") (pintype "unspecified"))
    )
    (net (code "37") (name "/SPI_SCK") (class "Default")
      (node (ref "U10") (pin "6") (pinfunction "CLK_6") (pintype "unspecified"))
      (node (ref "U3") (pin "15") (pinfunction "PA5_15") (pintype "unspecified"))
    )
    (net (code "38") (name "/STEP_A1") (class "Default")
      (node (ref "U3") (pin "20") (pinfunction "PB2_20") (pintype "unspecified"))
      (node (ref "U8") (pin "8") (pinfunction "I8_8") (pintype "input"))
    )
    (net (code "39") (name "/STEP_A2") (class "Default")
      (node (ref "U3") (pin "25") (pinfunction "PB12_25") (pintype "unspecified"))
      (node (ref "U8") (pin "7") (pinfunction "I7_7") (pintype "input"))
    )
    (net (code "40") (name "/STEP_A3") (class "Default")
      (node (ref "U3") (pin "26") (pinfunction "PB13_26") (pintype "unspecified"))
      (node (ref "U8") (pin "6") (pinfunction "I6_6") (pintype "input"))
    )
    (net (code "41") (name "/STEP_A4") (class "Default")
      (node (ref "U3") (pin "27") (pinfunction "PB14_27") (pintype "unspecified"))
      (node (ref "U8") (pin "5") (pinfunction "I5_5") (pintype "input"))
    )
    (net (code "42") (name "/STEP_B1") (class "Default")
      (node (ref "U3") (pin "28") (pinfunction "PB15_28") (pintype "unspecified"))
      (node (ref "U8") (pin "4") (pinfunction "I4_4") (pintype "input"))
    )
    (net (code "43") (name "/STEP_B2") (class "Default")
      (node (ref "U3") (pin "29") (pinfunction "PA8_29") (pintype "unspecified"))
      (node (ref "U8") (pin "3") (pinfunction "I3_3") (pintype "input"))
    )
    (net (code "44") (name "/STEP_B3") (class "Default")
      (node (ref "U3") (pin "32") (pinfunction "PA11_32") (pintype "unspecified"))
      (node (ref "U8") (pin "2") (pinfunction "I2_2") (pintype "input"))
    )
    (net (code "45") (name "/STEP_B4") (class "Default")
      (node (ref "U3") (pin "33") (pinfunction "PA12_33") (pintype "unspecified"))
      (node (ref "U8") (pin "1") (pinfunction "I1_1") (pintype "input"))
    )
    (net (code "46") (name "/SWCLK") (class "Default")
      (node (ref "H3") (pin "5") (pinfunction "5_5") (pintype "unspecified"))
      (node (ref "U3") (pin "37") (pinfunction "PA14_37") (pintype "unspecified"))
    )
    (net (code "47") (name "/SWDIO") (class "Default")
      (node (ref "H3") (pin "7") (pinfunction "7_7") (pintype "unspecified"))
      (node (ref "U3") (pin "34") (pinfunction "PA13_34") (pintype "unspecified"))
    )
    (net (code "48") (name "/UART1_RXD") (class "Default")
      (node (ref "H3") (pin "6") (pinfunction "6_6") (pintype "unspecified"))
      (node (ref "U3") (pin "31") (pinfunction "PA10_31") (pintype "unspecified"))
    )
    (net (code "49") (name "/UART1_TXD") (class "Default")
      (node (ref "H3") (pin "8") (pinfunction "8_8") (pintype "unspecified"))
      (node (ref "U3") (pin "30") (pinfunction "PA9_30") (pintype "unspecified"))
    )
    (net (code "50") (name "3V3") (class "Default")
      (node (ref "C1") (pin "1") (pinfunction "1_1") (pintype "unspecified"))
      (node (ref "C10") (pin "1") (pinfunction "1_1") (pintype "input"))
      (node (ref "C11") (pin "1") (pinfunction "1_1") (pintype "input"))
      (node (ref "C12") (pin "1") (pinfunction "1_1") (pintype "input"))
      (node (ref "C13") (pin "2") (pinfunction "2_2") (pintype "input"))
      (node (ref "C16") (pin "1") (pinfunction "1_1") (pintype "unspecified"))
      (node (ref "C17") (pin "2") (pinfunction "2_2") (pintype "input"))
      (node (ref "C2") (pin "1") (pinfunction "1_1") (pintype "unspecified"))
      (node (ref "C21") (pin "2") (pinfunction "2_2") (pintype "input"))
      (node (ref "C23") (pin "1") (pinfunction "1_1") (pintype "input"))
      (node (ref "C32") (pin "2") (pinfunction "2_2") (pintype "input"))
      (node (ref "C33") (pin "2") (pinfunction "2_2") (pintype "input"))
      (node (ref "C7") (pin "2") (pinfunction "2_2") (pintype "unspecified"))
      (node (ref "C8") (pin "1") (pinfunction "1_1") (pintype "input"))
      (node (ref "C9") (pin "1") (pinfunction "1_1") (pintype "unspecified"))
      (node (ref "D6") (pin "1") (pinfunction "C_1") (pintype "unspecified"))
      (node (ref "H3") (pin "3") (pinfunction "3_3") (pintype "unspecified"))
      (node (ref "H3") (pin "4") (pinfunction "4_4") (pintype "unspecified"))
      (node (ref "R1") (pin "2") (pinfunction "2_2") (pintype "input"))
      (node (ref "R10") (pin "1") (pinfunction "1_1") (pintype "input"))
      (node (ref "R12") (pin "2") (pinfunction "2_2") (pintype "input"))
      (node (ref "R13") (pin "2") (pinfunction "2_2") (pintype "input"))
      (node (ref "R14") (pin "1") (pinfunction "1_1") (pintype "input"))
      (node (ref "R15") (pin "2") (pinfunction "2_2") (pintype "input"))
      (node (ref "R20") (pin "1") (pinfunction "1_1") (pintype "input"))
      (node (ref "R21") (pin "2") (pinfunction "2_2") (pintype "input"))
      (node (ref "R27") (pin "2") (pinfunction "2_2") (pintype "input"))
      (node (ref "R30") (pin "2") (pinfunction "2_2") (pintype "input"))
      (node (ref "R39") (pin "2") (pinfunction "2_2") (pintype "input"))
      (node (ref "R5") (pin "2") (pinfunction "2_2") (pintype "input"))
      (node (ref "R9") (pin "1") (pinfunction "1_1") (pintype "input"))
      (node (ref "U10") (pin "8") (pinfunction "VCC_8") (pintype "unspecified"))
      (node (ref "U11") (pin "8") (pinfunction "VCC_8") (pintype "unspecified"))
      (node (ref "U16") (pin "2") (pinfunction "VCC_2") (pintype "input"))
      (node (ref "U18") (pin "2") (pinfunction "2_2") (pintype "unspecified"))
      (node (ref "U2") (pin "8") (pinfunction "VCC_8") (pintype "unspecified"))
      (node (ref "U26") (pin "2") (pinfunction "VOUT(TAB)_2") (pintype "unspecified"))
      (node (ref "U26") (pin "4") (pinfunction "TAB_4") (pintype "unspecified"))
      (node (ref "U3") (pin "1") (pinfunction "VBAT_1") (pintype "unspecified"))
      (node (ref "U3") (pin "24") (pinfunction "VDD_1_24") (pintype "unspecified"))
      (node (ref "U3") (pin "36") (pinfunction "VDD_2_36") (pintype "unspecified"))
      (node (ref "U3") (pin "48") (pinfunction "VDD_3_48") (pintype "unspecified"))
      (node (ref "U3") (pin "9") (pinfunction "VDDA_9") (pintype "unspecified"))
    )
    (net (code "51") (name "GND") (class "Default")
      (node (ref "C1") (pin "2") (pinfunction "2_2") (pintype "unspecified"))
      (node (ref "C10") (pin "2") (pinfunction "2_2") (pintype "input"))
      (node (ref "C11") (pin "2") (pinfunction "2_2") (pintype "input"))
      (node (ref "C12") (pin "2") (pinfunction "2_2") (pintype "input"))
      (node (ref "C13") (pin "1") (pinfunction "1_1") (pintype "input"))
      (node (ref "C14") (pin "1") (pinfunction "1_1") (pintype "unspecified"))
      (node (ref "C15") (pin "1") (pinfunction "1_1") (pintype "unspecified"))
      (node (ref "C16") (pin "2") (pinfunction "2_2") (pintype "unspecified"))
      (node (ref "C17") (pin "1") (pinfunction "1_1") (pintype "input"))
      (node (ref "C18") (pin "2") (pinfunction "2_2") (pintype "input"))
      (node (ref "C19") (pin "1") (pinfunction "1_1") (pintype "unspecified"))
      (node (ref "C2") (pin "2") (pinfunction "2_2") (pintype "unspecified"))
      (node (ref "C20") (pin "2") (pinfunction "2_2") (pintype "input"))
      (node (ref "C21") (pin "1") (pinfunction "1_1") (pintype "input"))
      (node (ref "C22") (pin "1") (pinfunction "1_1") (pintype "input"))
      (node (ref "C23") (pin "2") (pinfunction "2_2") (pintype "input"))
      (node (ref "C3") (pin "1") (pinfunction "1_1") (pintype "unspecified"))
      (node (ref "C32") (pin "1") (pinfunction "1_1") (pintype "input"))
      (node (ref "C33") (pin "1") (pinfunction "1_1") (pintype "input"))
      (node (ref "C34") (pin "1") (pinfunction "1_1") (pintype "unspecified"))
      (node (ref "C35") (pin "2") (pinfunction "2_2") (pintype "input"))
      (node (ref "C37") (pin "1") (pinfunction "1_1") (pintype "input"))
      (node (ref "C38") (pin "2") (pinfunction "2_2") (pintype "unspecified"))
      (node (ref "C39") (pin "2") (pinfunction "2_2") (pintype "unspecified"))
      (node (ref "C4") (pin "2") (pinfunction "2_2") (pintype "input"))
      (node (ref "C5") (pin "2") (pinfunction "2_2") (pintype "input"))
      (node (ref "C6") (pin "2") (pinfunction "2_2") (pintype "input"))
      (node (ref "C7") (pin "1") (pinfunction "1_1") (pintype "unspecified"))
      (node (ref "C8") (pin "2") (pinfunction "2_2") (pintype "input"))
      (node (ref "C9") (pin "2") (pinfunction "2_2") (pintype "unspecified"))
      (node (ref "D3") (pin "2") (pinfunction "A_2") (pintype "unspecified"))
      (node (ref "D6") (pin "2") (pinfunction "A_2") (pintype "unspecified"))
      (node (ref "DC1") (pin "2") (pinfunction "2_2") (pintype "unspecified"))
      (node (ref "DC1") (pin "3") (pinfunction "3_3") (pintype "unspecified"))
      (node (ref "H3") (pin "1") (pinfunction "1_1") (pintype "unspecified"))
      (node (ref "H3") (pin "2") (pinfunction "2_2") (pintype "unspecified"))
      (node (ref "LED1") (pin "1") (pinfunction "K_1") (pintype "unspecified"))
      (node (ref "M1") (pin "1") (pinfunction "1_1") (pintype "input"))
      (node (ref "M2") (pin "1") (pinfunction "1_1") (pintype "input"))
      (node (ref "M3") (pin "1") (pinfunction "1_1") (pintype "input"))
      (node (ref "M4") (pin "1") (pinfunction "1_1") (pintype "input"))
      (node (ref "Q1") (pin "2") (pinfunction "E_2") (pintype "unspecified"))
      (node (ref "R2") (pin "2") (pinfunction "2_2") (pintype "input"))
      (node (ref "R24") (pin "1") (pinfunction "1_1") (pintype "input"))
      (node (ref "R35") (pin "1") (pinfunction "1_1") (pintype "input"))
      (node (ref "R40") (pin "1") (pinfunction "1_1") (pintype "input"))
      (node (ref "R41") (pin "1") (pinfunction "1_1") (pintype "input"))
      (node (ref "R8") (pin "1") (pinfunction "1_1") (pintype "input"))
      (node (ref "SW1") (pin "1") (pinfunction "1_1") (pintype "unspecified"))
      (node (ref "U1") (pin "2") (pinfunction "2_2") (pintype "unspecified"))
      (node (ref "U10") (pin "4") (pinfunction "GND_4") (pintype "unspecified"))
      (node (ref "U11") (pin "1") (pinfunction "A0_1") (pintype "unspecified"))
      (node (ref "U11") (pin "2") (pinfunction "A1_2") (pintype "unspecified"))
      (node (ref "U11") (pin "3") (pinfunction "A2_3") (pintype "unspecified"))
      (node (ref "U11") (pin "4") (pinfunction "GND_4") (pintype "unspecified"))
      (node (ref "U11") (pin "7") (pinfunction "WP_7") (pintype "unspecified"))
      (node (ref "U13") (pin "1") (pinfunction "1_1") (pintype "input"))
      (node (ref "U13") (pin "2") (pinfunction "2_2") (pintype "input"))
      (node (ref "U14") (pin "2") (pinfunction "C_2") (pintype "unspecified"))
      (node (ref "U15") (pin "2") (pinfunction "E_2") (pintype "input"))
      (node (ref "U16") (pin "1") (pinfunction "GND_1") (pintype "input"))
      (node (ref "U16") (pin "9") (pinfunction "PGND_9") (pintype "input"))
      (node (ref "U17") (pin "2") (pinfunction "2_2") (pintype "unspecified"))
      (node (ref "U18") (pin "3") (pinfunction "3_3") (pintype "unspecified"))
      (node (ref "U2") (pin "4") (pinfunction "DI_4") (pintype "unspecified"))
      (node (ref "U2") (pin "5") (pinfunction "GND_5") (pintype "unspecified"))
      (node (ref "U24") (pin "6") (pinfunction "GND_6") (pintype "unspecified"))
      (node (ref "U24") (pin "9") (pinfunction "PowerPAD_9") (pintype "unspecified"))
      (node (ref "U26") (pin "1") (pinfunction "ADJ(GND)_1") (pintype "unspecified"))
      (node (ref "U3") (pin "23") (pinfunction "VSS_1_23") (pintype "unspecified"))
      (node (ref "U3") (pin "35") (pinfunction "VSS_2_35") (pintype "unspecified"))
      (node (ref "U3") (pin "47") (pinfunction "VSS_3_47") (pintype "unspecified"))
      (node (ref "U3") (pin "8") (pinfunction "VSSA_8") (pintype "unspecified"))
      (node (ref "U7") (pin "1") (pinfunction "1_1") (pintype "unspecified"))
      (node (ref "U8") (pin "9") (pinfunction "GND_9") (pintype "unspecified"))
      (node (ref "X1") (pin "2") (pinfunction "GND_2") (pintype "input"))
      (node (ref "X1") (pin "4") (pinfunction "GND_4") (pintype "input"))
    )
    (net (code "52") (name "Net-(CN4-Pad1)") (class "Default")
      (node (ref "CN4") (pin "1") (pinfunction "1_1") (pintype "unspecified"))
      (node (ref "RELAY1") (pin "2") (pinfunction "2_2") (pintype "input"))
    )
    (net (code "53") (name "Net-(CN4-Pad2)") (class "Default")
      (node (ref "CN4") (pin "2") (pinfunction "2_2") (pintype "unspecified"))
      (node (ref "RELAY1") (pin "5") (pinfunction "5_5") (pintype "input"))
    )
    (net (code "54") (name "Net-(CN4-Pad3)") (class "Default")
      (node (ref "CN4") (pin "3") (pinfunction "3_3") (pintype "unspecified"))
      (node (ref "RELAY1") (pin "3") (pinfunction "3_3") (pintype "input"))
    )
    (net (code "55") (name "Net-(D2-A)") (class "Default")
      (node (ref "D2") (pin "2") (pinfunction "A_2") (pintype "unspecified"))
      (node (ref "RELAY1") (pin "4") (pinfunction "4_4") (pintype "input"))
      (node (ref "U12") (pin "1") (pinfunction "C_1") (pintype "unspecified"))
      (node (ref "U15") (pin "3") (pinfunction "C_3") (pintype "input"))
    )
    (net (code "56") (name "Net-(D3-K)") (class "Default")
      (node (ref "C27") (pin "2") (pinfunction "2_2") (pintype "input"))
      (node (ref "D3") (pin "1") (pinfunction "K_1") (pintype "unspecified"))
      (node (ref "L1") (pin "2") (pinfunction "2_2") (pintype "unspecified"))
      (node (ref "U24") (pin "8") (pinfunction "PH_8") (pintype "unspecified"))
    )
    (net (code "57") (name "Net-(LED1-A)") (class "Default")
      (node (ref "LED1") (pin "2") (pinfunction "A_2") (pintype "unspecified"))
      (node (ref "R30") (pin "1") (pinfunction "1_1") (pintype "input"))
    )
    (net (code "58") (name "Net-(Q1-B)") (class "Default")
      (node (ref "Q1") (pin "1") (pinfunction "B_1") (pintype "unspecified"))
      (node (ref "R7") (pin "2") (pinfunction "2_2") (pintype "unspecified"))
      (node (ref "R8") (pin "2") (pinfunction "2_2") (pintype "input"))
    )
    (net (code "59") (name "Net-(Q1-C)") (class "Default")
      (node (ref "Q1") (pin "3") (pinfunction "C_3") (pintype "unspecified"))
      (node (ref "R5") (pin "1") (pinfunction "1_1") (pintype "input"))
      (node (ref "U2") (pin "2") (pinfunction "RE#_2") (pintype "unspecified"))
      (node (ref "U2") (pin "3") (pinfunction "DE_3") (pintype "unspecified"))
    )
    (net (code "60") (name "Net-(Q2-Pad1)") (class "Default")
      (node (ref "Q2") (pin "1") (pinfunction "1_1") (pintype "input"))
      (node (ref "R15") (pin "1") (pinfunction "1_1") (pintype "input"))
    )
    (net (code "61") (name "Net-(Q2-Pad3)") (class "Default")
      (node (ref "Q2") (pin "3") (pinfunction "3_3") (pintype "input"))
      (node (ref "R16") (pin "2") (pinfunction "2_2") (pintype "input"))
      (node (ref "R18") (pin "1") (pinfunction "1_1") (pintype "input"))
    )
    (net (code "62") (name "Net-(Q3-Pad1)") (class "Default")
      (node (ref "Q3") (pin "1") (pinfunction "1_1") (pintype "input"))
      (node (ref "R21") (pin "1") (pinfunction "1_1") (pintype "input"))
    )
    (net (code "63") (name "Net-(Q3-Pad3)") (class "Default")
      (node (ref "Q3") (pin "3") (pinfunction "3_3") (pintype "input"))
      (node (ref "R22") (pin "2") (pinfunction "2_2") (pintype "input"))
      (node (ref "R25") (pin "1") (pinfunction "1_1") (pintype "input"))
    )
    (net (code "64") (name "Net-(U2-A)") (class "Default")
      (node (ref "F2") (pin "1") (pinfunction "1_1") (pintype "unspecified"))
      (node (ref "R9") (pin "2") (pinfunction "2_2") (pintype "input"))
      (node (ref "U2") (pin "6") (pinfunction "A_6") (pintype "unspecified"))
      (node (ref "U4") (pin "1") (pinfunction "1_1") (pintype "unspecified"))
      (node (ref "U7") (pin "2") (pinfunction "2_2") (pintype "unspecified"))
    )
    (net (code "65") (name "Net-(U2-B)") (class "Default")
      (node (ref "F1") (pin "1") (pinfunction "1_1") (pintype "unspecified"))
      (node (ref "R2") (pin "1") (pinfunction "1_1") (pintype "input"))
      (node (ref "U1") (pin "1") (pinfunction "1_1") (pintype "unspecified"))
      (node (ref "U2") (pin "7") (pinfunction "B_7") (pintype "unspecified"))
      (node (ref "U4") (pin "2") (pinfunction "2_2") (pintype "unspecified"))
    )
    (net (code "66") (name "Net-(U9-A)") (class "Default")
      (node (ref "R10") (pin "2") (pinfunction "2_2") (pintype "input"))
      (node (ref "U9") (pin "2") (pinfunction "A_2") (pintype "unspecified"))
    )
    (net (code "67") (name "Net-(U11-SDA)") (class "Default")
      (node (ref "R13") (pin "1") (pinfunction "1_1") (pintype "input"))
      (node (ref "U11") (pin "5") (pinfunction "SDA_5") (pintype "unspecified"))
    )
    (net (code "68") (name "Net-(U12-A)") (class "Default")
      (node (ref "R17") (pin "2") (pinfunction "2_2") (pintype "input"))
      (node (ref "U12") (pin "2") (pinfunction "A_2") (pintype "unspecified"))
    )
    (net (code "69") (name "Net-(U14-A)") (class "Default")
      (node (ref "R19") (pin "1") (pinfunction "1_1") (pintype "input"))
      (node (ref "U14") (pin "1") (pinfunction "A_1") (pintype "unspecified"))
    )
    (net (code "70") (name "Net-(U14-E)") (class "Default")
      (node (ref "R23") (pin "2") (pinfunction "2_2") (pintype "unspecified"))
      (node (ref "U14") (pin "3") (pinfunction "E_3") (pintype "unspecified"))
    )
    (net (code "71") (name "Net-(U15-B)") (class "Default")
      (node (ref "R23") (pin "1") (pinfunction "1_1") (pintype "unspecified"))
      (node (ref "R24") (pin "2") (pinfunction "2_2") (pintype "input"))
      (node (ref "U15") (pin "1") (pinfunction "B_1") (pintype "input"))
    )
    (net (code "72") (name "Net-(U24-BOOT)") (class "Default")
      (node (ref "C27") (pin "1") (pinfunction "1_1") (pintype "input"))
      (node (ref "U24") (pin "1") (pinfunction "BOOT_1") (pintype "unspecified"))
    )
    (net (code "73") (name "Net-(U24-VSENSE)") (class "Default")
      (node (ref "R34") (pin "2") (pinfunction "2_2") (pintype "input"))
      (node (ref "R35") (pin "2") (pinfunction "2_2") (pintype "input"))
      (node (ref "U24") (pin "4") (pinfunction "VSENSE_4") (pintype "unspecified"))
    )
    (net (code "74") (name "VIN") (class "Default")
      (node (ref "D4") (pin "2") (pinfunction "A_2") (pintype "unspecified"))
      (node (ref "DC1") (pin "1") (pinfunction "1_1") (pintype "unspecified"))
      (node (ref "R38") (pin "2") (pinfunction "2_2") (pintype "unspecified"))
    )
    (net (code "75") (name "unconnected-(U3-BOOT0-Pad44)") (class "Default")
      (node (ref "U3") (pin "44") (pinfunction "BOOT0_44") (pintype "unspecified+no_connect"))
    )
    (net (code "76") (name "unconnected-(U3-PA15-Pad38)") (class "Default")
      (node (ref "U3") (pin "38") (pinfunction "PA15_38") (pintype "unspecified+no_connect"))
    )
    (net (code "77") (name "unconnected-(U3-PB3-Pad39)") (class "Default")
      (node (ref "U3") (pin "39") (pinfunction "PB3_39") (pintype "unspecified+no_connect"))
    )
    (net (code "78") (name "unconnected-(U3-PB8-Pad45)") (class "Default")
      (node (ref "U3") (pin "45") (pinfunction "PB8_45") (pintype "unspecified+no_connect"))
    )
    (net (code "79") (name "unconnected-(U3-PB9-Pad46)") (class "Default")
      (node (ref "U3") (pin "46") (pinfunction "PB9_46") (pintype "unspecified+no_connect"))
    )
    (net (code "80") (name "unconnected-(U3-PC14_OSC32_IN-Pad3)") (class "Default")
      (node (ref "U3") (pin "3") (pinfunction "PC14_OSC32_IN_3") (pintype "unspecified+no_connect"))
    )
    (net (code "81") (name "unconnected-(U3-PC15_OSC32_OUT-Pad4)") (class "Default")
      (node (ref "U3") (pin "4") (pinfunction "PC15_OSC32_OUT_4") (pintype "unspecified+no_connect"))
    )
    (net (code "82") (name "unconnected-(U10-IO2-Pad3)") (class "Default")
      (node (ref "U10") (pin "3") (pinfunction "IO2_3") (pintype "unspecified+no_connect"))
    )
    (net (code "83") (name "unconnected-(U10-IO3-Pad7)") (class "Default")
      (node (ref "U10") (pin "7") (pinfunction "IO3_7") (pintype "unspecified+no_connect"))
    )
    (net (code "84") (name "unconnected-(U16-NC-Pad8)") (class "Default")
      (node (ref "U16") (pin "8") (pinfunction "NC_8") (pintype "input+no_connect"))
    )
    (net (code "85") (name "unconnected-(U24-ENA-Pad5)") (class "Default")
      (node (ref "U24") (pin "5") (pinfunction "ENA_5") (pintype "unspecified+no_connect"))
    )
    (net (code "86") (name "unconnected-(U24-NC-Pad2)") (class "Default")
      (node (ref "U24") (pin "2") (pinfunction "NC_2") (pintype "unspecified+no_connect"))
    )
    (net (code "87") (name "unconnected-(U24-NC-Pad3)") (class "Default")
      (node (ref "U24") (pin "3") (pinfunction "NC_3") (pintype "unspecified+no_connect"))
    )
  )
)
